# RemoteSch_1R1.net
KiCad netlist of a schematic drawn in Altium Designer
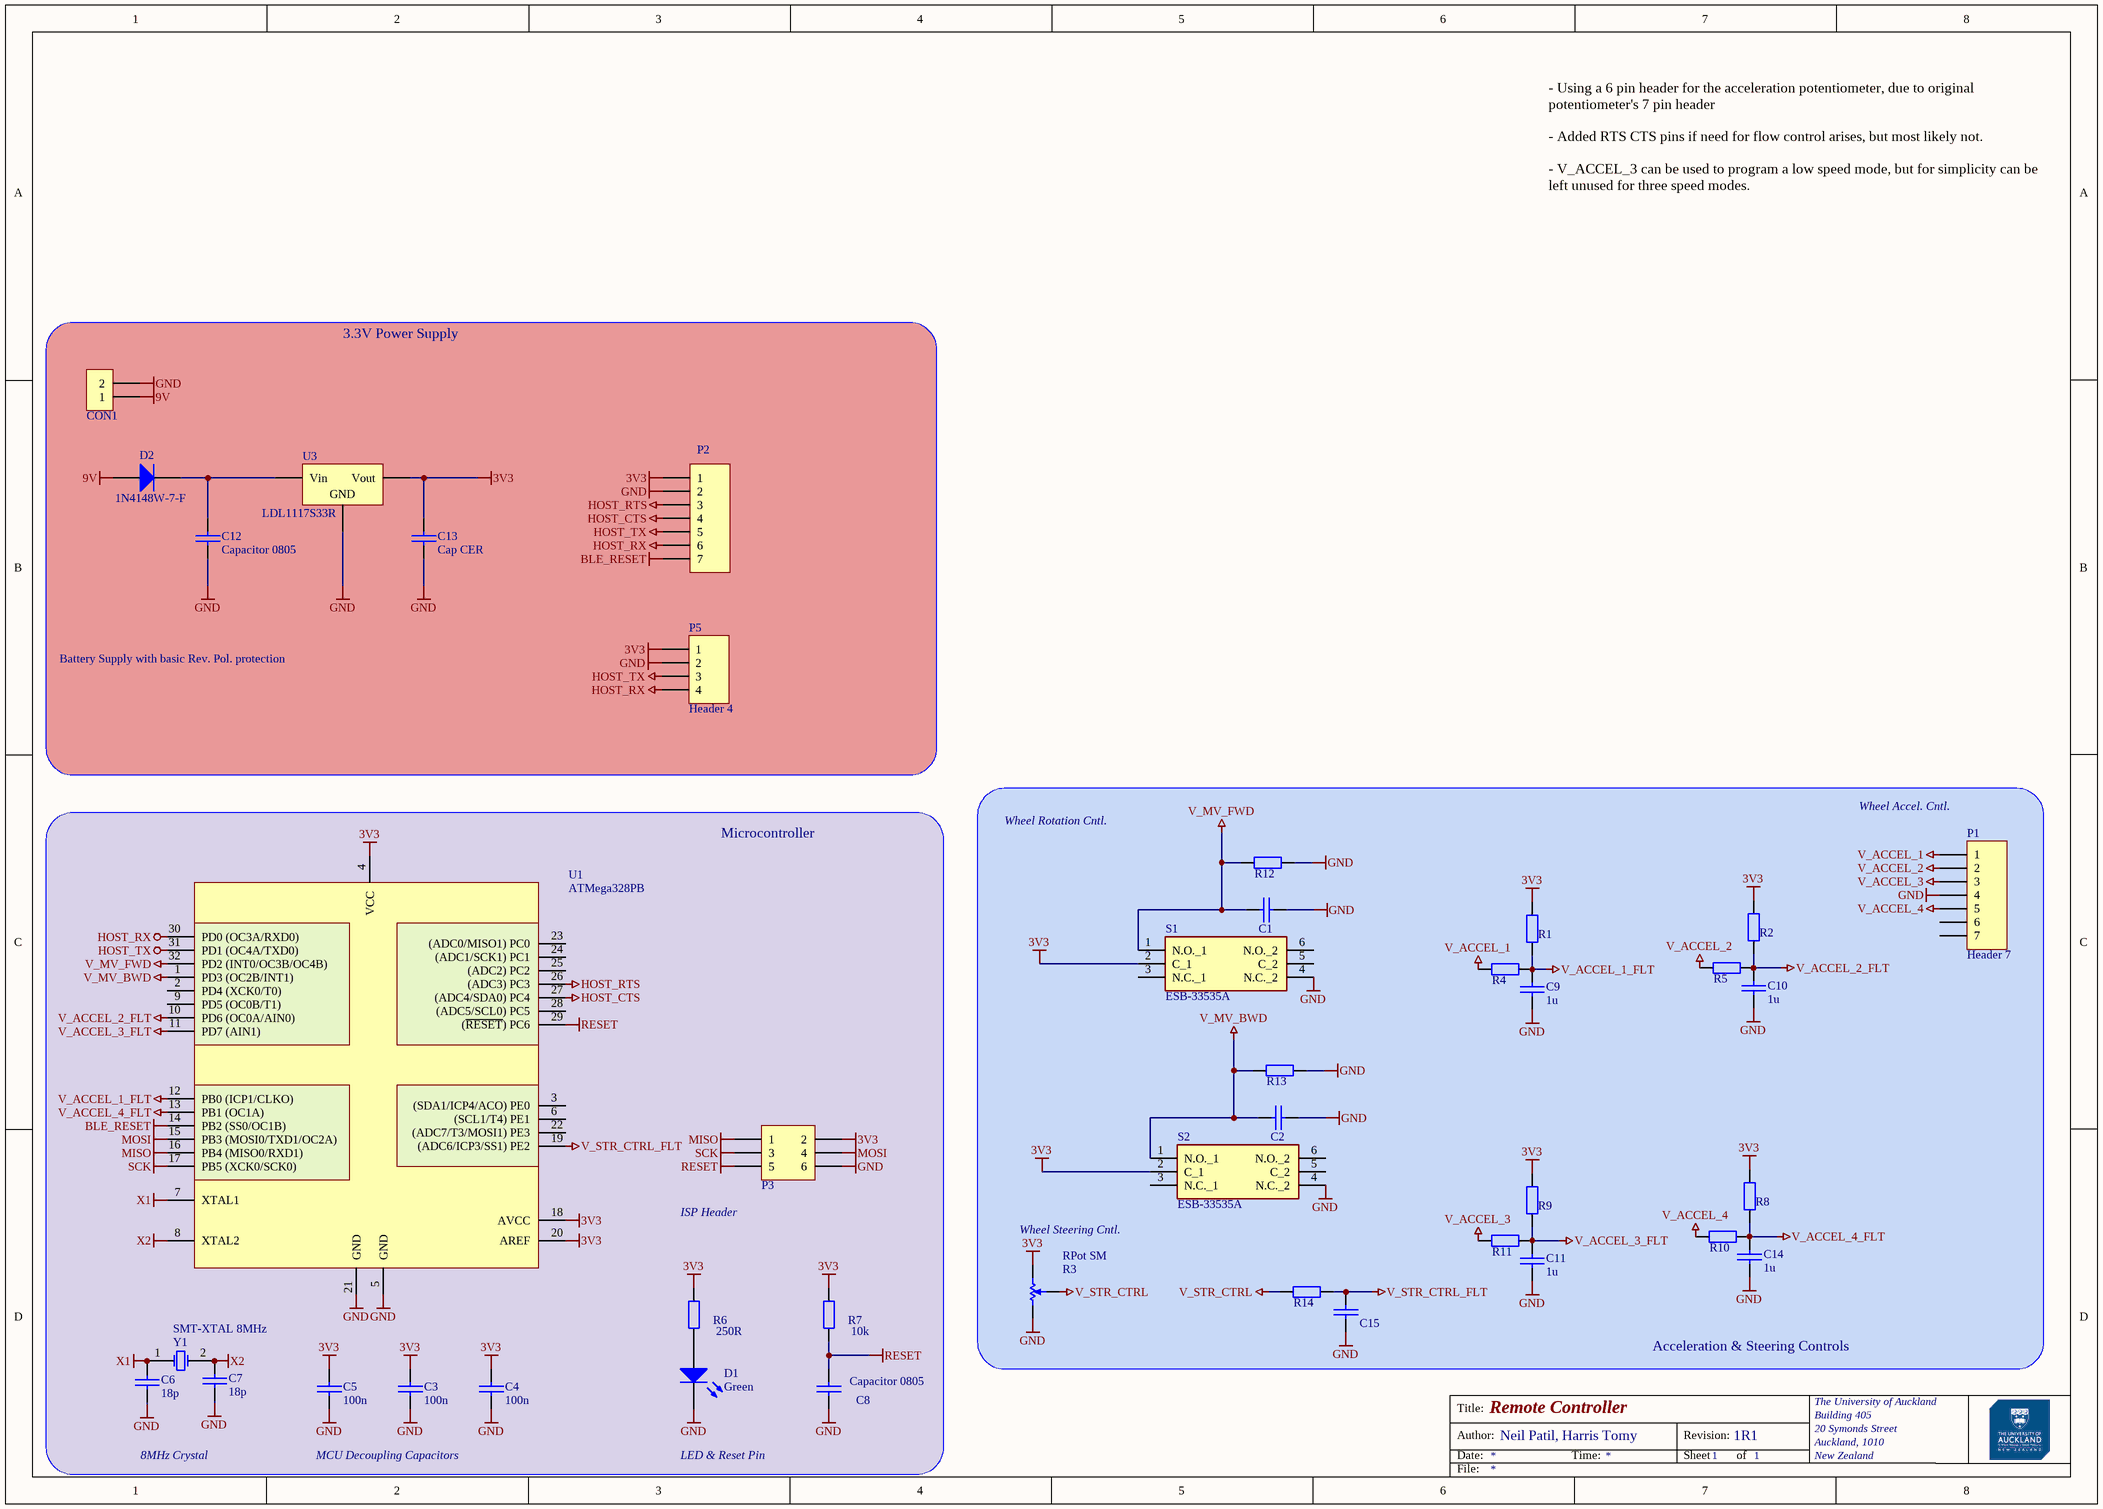
[diagram p0: RemoteSch_1R1.SchDoc]

(export (version "E")
  (design (tool "Eeschema 10.0.6"))
  (components
    (comp (ref "C1")
      (value "Capacitor 0805")
      (footprint "C0805")
      (description "CCAP0805")
      (libsource (lib "CommonDevices_V1") (part "CCAP0805"))
    )
    (comp (ref "C2")
      (value "Capacitor 0805")
      (footprint "C0805")
      (description "CCAP0805")
      (libsource (lib "CommonDevices_V1") (part "CCAP0805"))
    )
    (comp (ref "C3")
      (value "100n")
      (footprint "C0805")
      (description "CCAP0805")
      (libsource (lib "CommonDevices_V1") (part "CCAP0805"))
    )
    (comp (ref "C4")
      (value "100n")
      (footprint "C0805")
      (description "CCAP0805")
      (libsource (lib "CommonDevices_V1") (part "CCAP0805"))
    )
    (comp (ref "C5")
      (value "100n")
      (footprint "C0805")
      (description "CCAP0805")
      (libsource (lib "CommonDevices_V1") (part "CCAP0805"))
    )
    (comp (ref "C6")
      (value "18p")
      (footprint "C0805")
      (description "CCAP0805")
      (libsource (lib "CommonDevices_V1") (part "CCAP0805"))
    )
    (comp (ref "C7")
      (value "18p")
      (footprint "C0805")
      (description "CCAP0805")
      (libsource (lib "CommonDevices_V1") (part "CCAP0805"))
    )
    (comp (ref "C8")
      (value "Capacitor 0805")
      (footprint "C0805")
      (description "CCAP0805")
      (libsource (lib "CommonDevices_V1") (part "CCAP0805"))
    )
    (comp (ref "C9")
      (value "1u")
      (footprint "C0805")
      (description "CCAP0805")
      (libsource (lib "CommonDevices_V1") (part "CCAP0805"))
    )
    (comp (ref "C10")
      (value "1u")
      (footprint "C0805")
      (description "CCAP0805")
      (libsource (lib "CommonDevices_V1") (part "CCAP0805"))
    )
    (comp (ref "C11")
      (value "1u")
      (footprint "C0805")
      (description "CCAP0805")
      (libsource (lib "CommonDevices_V1") (part "CCAP0805"))
    )
    (comp (ref "C12")
      (value "Capacitor 0805")
      (footprint "C0805")
      (description "CCAP0805")
      (libsource (lib "CommonDevices_V1") (part "CCAP0805"))
    )
    (comp (ref "C13")
      (value "Cap CER")
      (footprint "C1206")
      (description "CAP CER 0.1UF 100V C0G 1206")
      (fields (field (name "MPN") "C3216C0G2A104J160AC") (field (name "MANUFACTURER") "TDK Corporation"))
      (libsource (lib "E209_Lib") (part "Cap CER Decoup C3216C0G2A104J160AC"))
    )
    (comp (ref "C14")
      (value "1u")
      (footprint "C0805")
      (description "CCAP0805")
      (libsource (lib "CommonDevices_V1") (part "CCAP0805"))
    )
    (comp (ref "C15")
      (value "Capacitor 0805")
      (footprint "C0805")
      (description "CCAP0805")
      (libsource (lib "CommonDevices_V1") (part "CCAP0805"))
    )
    (comp (ref "CON1")
      (value "Header 2X1")
      (footprint "HDR2X1_2P54")
      (libsource (lib "CommonDevices_V1") (part "HDR2X1"))
    )
    (comp (ref "D1")
      (value "Green")
      (footprint "LED")
      (description "Typical throughole GaAs LED with 2.54mm pitch")
      (fields (field (name "MANUFACTURER") "Generic Components") (field (name "PUBLISHER") "Altium Limited"))
      (libsource (lib "EE209_Library") (part "LED_TH_2P54"))
    )
    (comp (ref "D2")
      (value "1N4148W-7-F")
      (footprint "SOD123")
      (description "DIODE GEN PURP 100V 300MA SOD123")
      (fields
        (field (name "MANUFACTURER") "Diodes Incorporated")
        (field (name "MANUFACTURER PART NUMBER") "1N4148W-13-F")
      )
      (libsource (lib "EE209_Library") (part "1N4148_SMT_SOD123"))
    )
    (comp (ref "P1")
      (value "Header 7")
      (footprint "HDR1X7")
      (description "Header, 7-Pin")
      (fields (field (name "PUBLISHER") "Altium Limited"))
      (libsource (lib "Miscellaneous Connectors") (part "Header 7"))
    )
    (comp (ref "P2")
      (value "Header 7")
      (footprint "HDR1X7")
      (description "Header, 7-Pin")
      (fields (field (name "PUBLISHER") "Altium Limited"))
      (libsource (lib "Miscellaneous Connectors") (part "Header 7"))
    )
    (comp (ref "P3")
      (value "HDR3X2")
      (footprint "HDR2X3_2P54")
      (description "Header, 3-Pin, Dual row")
      (libsource (lib "CommonDevices_V1") (part "HDR3X2"))
    )
    (comp (ref "P5")
      (value "Header 4")
      (footprint "HDR1X4")
      (description "Header, 4-Pin")
      (fields (field (name "PUBLISHER") "Altium Limited"))
      (libsource (lib "Miscellaneous Connectors") (part "Header 4"))
    )
    (comp (ref "R1")
      (value "Resistor 0805")
      (footprint "R0805")
      (description "RES0805")
      (libsource (lib "CommonDevices_V1") (part "RES0805"))
    )
    (comp (ref "R2")
      (value "Resistor 0805")
      (footprint "R0805")
      (description "RES0805")
      (libsource (lib "CommonDevices_V1") (part "RES0805"))
    )
    (comp (ref "R3")
      (value "RPot SM")
      (footprint "POT4MM-2")
      (description "Square Trimming Potentiometer")
      (fields (field (name "PUBLISHER") "Altium Limited"))
      (libsource (lib "Miscellaneous Devices") (part "RPot SM"))
    )
    (comp (ref "R4")
      (value "Resistor 0805")
      (footprint "R0805")
      (description "RES0805")
      (libsource (lib "") (part "RES0805_1"))
    )
    (comp (ref "R5")
      (value "Resistor 0805")
      (footprint "R0805")
      (description "RES0805")
      (libsource (lib "") (part "RES0805_1"))
    )
    (comp (ref "R6")
      (value "250R")
      (footprint "R0805")
      (description "RES0805")
      (libsource (lib "CommonDevices_V1") (part "RES0805"))
    )
    (comp (ref "R7")
      (value "10k")
      (footprint "R0805")
      (description "RES0805")
      (libsource (lib "CommonDevices_V1") (part "RES0805"))
    )
    (comp (ref "R8")
      (value "Resistor 0805")
      (footprint "R0805")
      (description "RES0805")
      (libsource (lib "CommonDevices_V1") (part "RES0805"))
    )
    (comp (ref "R9")
      (value "Resistor 0805")
      (footprint "R0805")
      (description "RES0805")
      (libsource (lib "CommonDevices_V1") (part "RES0805"))
    )
    (comp (ref "R10")
      (value "Resistor 0805")
      (footprint "R0805")
      (description "RES0805")
      (libsource (lib "") (part "RES0805_1"))
    )
    (comp (ref "R11")
      (value "Resistor 0805")
      (footprint "R0805")
      (description "RES0805")
      (libsource (lib "") (part "RES0805_1"))
    )
    (comp (ref "R12")
      (value "Resistor 0805")
      (footprint "R0805")
      (description "RES0805")
      (libsource (lib "") (part "RES0805_1"))
    )
    (comp (ref "R13")
      (value "Resistor 0805")
      (footprint "R0805")
      (description "RES0805")
      (libsource (lib "") (part "RES0805_1"))
    )
    (comp (ref "R14")
      (value "Resistor 0805")
      (footprint "R0805")
      (description "RES0805")
      (libsource (lib "") (part "RES0805_2"))
    )
    (comp (ref "S1")
      (value "ESB-33535A")
      (footprint "ESB33535A")
      (description "Switch")
      (fields (field (name "MOUSER PART NUMBER") "667-ESB-33535A"))
      (libsource (lib "ESB-3353A") (part "ESB-33535A"))
    )
    (comp (ref "S2")
      (value "ESB-33535A")
      (footprint "ESB33535A")
      (description "Switch")
      (fields (field (name "MOUSER PART NUMBER") "667-ESB-33535A"))
      (libsource (lib "ESB-3353A") (part "ESB-33535A"))
    )
    (comp (ref "U1")
      (value "ATMega328PB")
      (footprint "TQFP32")
      (description "IC MCU 8BIT 32KB FLASH 32TQFP")
      (libsource (lib "CommonDevices_V1") (part "ATMega328PB"))
    )
    (comp (ref "U3")
      (value "LDL1117S33R")
      (footprint "SOT223L")
      (description "IC REG LINEAR 3.3V 1.2A SOT223")
      (fields (field (name "MANUFACTURER") "STMicroelectronics"))
      (libsource (lib "E209_Lib") (part "LDO LDL1117S33R"))
    )
    (comp (ref "Y1")
      (value "SMT-XTAL 8MHz")
      (footprint "HC49-US")
      (description "9C-16.000MAAJ-T crystal 16.0000MHZ 18PF SMD")
      (fields
        (field (name "MANUFACTURER") "TXC CORPORATION")
        (field (name "MANUFACTURER PART NUMBER") "9C-16.000MAAJ-T")
      )
      (libsource (lib "EE209_Library") (part "TXC9C-16_XTAL_SMT"))
    )
  )
  (nets
    (net (code "1") (name "3V3") (class "Default")
      (node (ref "C13") (pin "2") (pinfunction "2_2") (pintype "passive"))
      (node (ref "C3") (pin "2") (pinfunction "2_2") (pintype "passive"))
      (node (ref "C4") (pin "2") (pinfunction "2_2") (pintype "passive"))
      (node (ref "C5") (pin "2") (pinfunction "2_2") (pintype "passive"))
      (node (ref "P2") (pin "1") (pinfunction "1_1") (pintype "passive"))
      (node (ref "P3") (pin "2") (pinfunction "2_2") (pintype "passive"))
      (node (ref "P5") (pin "1") (pinfunction "1_1") (pintype "passive"))
      (node (ref "R1") (pin "2") (pinfunction "2_2") (pintype "passive"))
      (node (ref "R2") (pin "2") (pinfunction "2_2") (pintype "passive"))
      (node (ref "R3") (pin "CW") (pinfunction "+_CW") (pintype "passive"))
      (node (ref "R6") (pin "2") (pinfunction "2_2") (pintype "passive"))
      (node (ref "R7") (pin "2") (pinfunction "2_2") (pintype "passive"))
      (node (ref "R8") (pin "2") (pinfunction "2_2") (pintype "passive"))
      (node (ref "R9") (pin "2") (pinfunction "2_2") (pintype "passive"))
      (node (ref "S1") (pin "2") (pinfunction "C_1_2") (pintype "passive"))
      (node (ref "S2") (pin "2") (pinfunction "C_1_2") (pintype "passive"))
      (node (ref "U1") (pin "18") (pinfunction "AVCC_18") (pintype "passive"))
      (node (ref "U1") (pin "20") (pinfunction "AREF_20") (pintype "passive"))
      (node (ref "U1") (pin "4") (pinfunction "VCC_4") (pintype "passive"))
      (node (ref "U3") (pin "2") (pinfunction "Vout_2") (pintype "passive"))
    )
    (net (code "2") (name "9V") (class "Default")
      (node (ref "CON1") (pin "1") (pinfunction "1_1") (pintype "passive"))
      (node (ref "D2") (pin "1") (pinfunction "A_1") (pintype "passive"))
    )
    (net (code "3") (name "BLE_RESET") (class "Default")
      (node (ref "P2") (pin "7") (pinfunction "7_7") (pintype "passive"))
      (node (ref "U1") (pin "14") (pinfunction "PB2_(SS0/OC1B)_14") (pintype "passive"))
    )
    (net (code "4") (name "GND") (class "Default")
      (node (ref "C1") (pin "1") (pinfunction "1_1") (pintype "passive"))
      (node (ref "C10") (pin "1") (pinfunction "1_1") (pintype "passive"))
      (node (ref "C11") (pin "1") (pinfunction "1_1") (pintype "passive"))
      (node (ref "C12") (pin "1") (pinfunction "1_1") (pintype "passive"))
      (node (ref "C13") (pin "1") (pinfunction "1_1") (pintype "passive"))
      (node (ref "C14") (pin "1") (pinfunction "1_1") (pintype "passive"))
      (node (ref "C15") (pin "1") (pinfunction "1_1") (pintype "passive"))
      (node (ref "C2") (pin "1") (pinfunction "1_1") (pintype "passive"))
      (node (ref "C3") (pin "1") (pinfunction "1_1") (pintype "passive"))
      (node (ref "C4") (pin "1") (pinfunction "1_1") (pintype "passive"))
      (node (ref "C5") (pin "1") (pinfunction "1_1") (pintype "passive"))
      (node (ref "C6") (pin "2") (pinfunction "2_2") (pintype "passive"))
      (node (ref "C7") (pin "2") (pinfunction "2_2") (pintype "passive"))
      (node (ref "C8") (pin "1") (pinfunction "1_1") (pintype "passive"))
      (node (ref "C9") (pin "1") (pinfunction "1_1") (pintype "passive"))
      (node (ref "CON1") (pin "2") (pinfunction "2_2") (pintype "passive"))
      (node (ref "D1") (pin "2") (pinfunction "K_2") (pintype "passive"))
      (node (ref "P1") (pin "4") (pinfunction "4_4") (pintype "passive"))
      (node (ref "P2") (pin "2") (pinfunction "2_2") (pintype "passive"))
      (node (ref "P3") (pin "6") (pinfunction "6_6") (pintype "passive"))
      (node (ref "P5") (pin "2") (pinfunction "2_2") (pintype "passive"))
      (node (ref "R12") (pin "1") (pinfunction "1_1") (pintype "passive"))
      (node (ref "R13") (pin "1") (pinfunction "1_1") (pintype "passive"))
      (node (ref "R3") (pin "CCW") (pinfunction "-_CCW") (pintype "passive"))
      (node (ref "S1") (pin "4") (pinfunction "N.C._2_4") (pintype "passive"))
      (node (ref "S2") (pin "4") (pinfunction "N.C._2_4") (pintype "passive"))
      (node (ref "U1") (pin "21") (pinfunction "GND_21") (pintype "passive"))
      (node (ref "U1") (pin "5") (pinfunction "GND_5") (pintype "passive"))
      (node (ref "U3") (pin "1") (pinfunction "GND_1") (pintype "passive"))
    )
    (net (code "5") (name "HOST_CTS") (class "Default")
      (node (ref "P2") (pin "4") (pinfunction "4_4") (pintype "passive"))
      (node (ref "U1") (pin "27") (pinfunction "(ADC4/SDA0)_PC4_27") (pintype "passive"))
    )
    (net (code "6") (name "HOST_RTS") (class "Default")
      (node (ref "P2") (pin "3") (pinfunction "3_3") (pintype "passive"))
      (node (ref "U1") (pin "26") (pinfunction "(ADC3)_PC3_26") (pintype "passive"))
    )
    (net (code "7") (name "HOST_RX") (class "Default")
      (node (ref "P2") (pin "6") (pinfunction "6_6") (pintype "passive"))
      (node (ref "P5") (pin "4") (pinfunction "4_4") (pintype "passive"))
      (node (ref "U1") (pin "30") (pinfunction "PD0_(OC3A/RXD0)_30") (pintype "passive"))
    )
    (net (code "8") (name "HOST_TX") (class "Default")
      (node (ref "P2") (pin "5") (pinfunction "5_5") (pintype "passive"))
      (node (ref "P5") (pin "3") (pinfunction "3_3") (pintype "passive"))
      (node (ref "U1") (pin "31") (pinfunction "PD1_(OC4A/TXD0)_31") (pintype "passive"))
    )
    (net (code "9") (name "MISO") (class "Default")
      (node (ref "P3") (pin "1") (pinfunction "1_1") (pintype "passive"))
      (node (ref "U1") (pin "16") (pinfunction "PB4_(MISO0/RXD1)_16") (pintype "passive"))
    )
    (net (code "10") (name "MOSI") (class "Default")
      (node (ref "P3") (pin "4") (pinfunction "4_4") (pintype "passive"))
      (node (ref "U1") (pin "15") (pinfunction "PB3_(MOSI0/TXD1/OC2A)_15") (pintype "passive"))
    )
    (net (code "11") (name "Net-(D1-A)") (class "Default")
      (node (ref "D1") (pin "1") (pinfunction "A_1") (pintype "passive"))
      (node (ref "R6") (pin "1") (pinfunction "1_1") (pintype "passive"))
    )
    (net (code "12") (name "Net-(D2-K)") (class "Default")
      (node (ref "C12") (pin "2") (pinfunction "2_2") (pintype "passive"))
      (node (ref "D2") (pin "2") (pinfunction "K_2") (pintype "passive"))
      (node (ref "U3") (pin "3") (pinfunction "Vin_3") (pintype "passive"))
    )
    (net (code "13") (name "RESET") (class "Default")
      (node (ref "C8") (pin "2") (pinfunction "2_2") (pintype "passive"))
      (node (ref "P3") (pin "5") (pinfunction "5_5") (pintype "passive"))
      (node (ref "R7") (pin "1") (pinfunction "1_1") (pintype "passive"))
      (node (ref "U1") (pin "29") (pinfunction "(~{RESET})_PC6_29") (pintype "passive"))
    )
    (net (code "14") (name "SCK") (class "Default")
      (node (ref "P3") (pin "3") (pinfunction "3_3") (pintype "passive"))
      (node (ref "U1") (pin "17") (pinfunction "PB5_(XCK0/SCK0)_17") (pintype "passive"))
    )
    (net (code "15") (name "V_ACCEL_1") (class "Default")
      (node (ref "P1") (pin "1") (pinfunction "1_1") (pintype "passive"))
      (node (ref "R4") (pin "2") (pinfunction "2_2") (pintype "passive"))
    )
    (net (code "16") (name "V_ACCEL_1_FLT") (class "Default")
      (node (ref "C9") (pin "2") (pinfunction "2_2") (pintype "passive"))
      (node (ref "R1") (pin "1") (pinfunction "1_1") (pintype "passive"))
      (node (ref "R4") (pin "1") (pinfunction "1_1") (pintype "passive"))
      (node (ref "U1") (pin "12") (pinfunction "PB0_(ICP1/CLKO)_12") (pintype "passive"))
    )
    (net (code "17") (name "V_ACCEL_2") (class "Default")
      (node (ref "P1") (pin "2") (pinfunction "2_2") (pintype "passive"))
      (node (ref "R5") (pin "2") (pinfunction "2_2") (pintype "passive"))
    )
    (net (code "18") (name "V_ACCEL_2_FLT") (class "Default")
      (node (ref "C10") (pin "2") (pinfunction "2_2") (pintype "passive"))
      (node (ref "R2") (pin "1") (pinfunction "1_1") (pintype "passive"))
      (node (ref "R5") (pin "1") (pinfunction "1_1") (pintype "passive"))
      (node (ref "U1") (pin "10") (pinfunction "PD6_(OC0A/AIN0)_10") (pintype "passive"))
    )
    (net (code "19") (name "V_ACCEL_3") (class "Default")
      (node (ref "P1") (pin "3") (pinfunction "3_3") (pintype "passive"))
      (node (ref "R11") (pin "2") (pinfunction "2_2") (pintype "passive"))
    )
    (net (code "20") (name "V_ACCEL_3_FLT") (class "Default")
      (node (ref "C11") (pin "2") (pinfunction "2_2") (pintype "passive"))
      (node (ref "R11") (pin "1") (pinfunction "1_1") (pintype "passive"))
      (node (ref "R9") (pin "1") (pinfunction "1_1") (pintype "passive"))
      (node (ref "U1") (pin "11") (pinfunction "PD7_(AIN1)_11") (pintype "passive"))
    )
    (net (code "21") (name "V_ACCEL_4") (class "Default")
      (node (ref "P1") (pin "5") (pinfunction "5_5") (pintype "passive"))
      (node (ref "R10") (pin "2") (pinfunction "2_2") (pintype "passive"))
    )
    (net (code "22") (name "V_ACCEL_4_FLT") (class "Default")
      (node (ref "C14") (pin "2") (pinfunction "2_2") (pintype "passive"))
      (node (ref "R10") (pin "1") (pinfunction "1_1") (pintype "passive"))
      (node (ref "R8") (pin "1") (pinfunction "1_1") (pintype "passive"))
      (node (ref "U1") (pin "13") (pinfunction "PB1_(OC1A)_13") (pintype "passive"))
    )
    (net (code "23") (name "V_MV_BWD") (class "Default")
      (node (ref "C2") (pin "2") (pinfunction "2_2") (pintype "passive"))
      (node (ref "R13") (pin "2") (pinfunction "2_2") (pintype "passive"))
      (node (ref "S2") (pin "1") (pinfunction "N.O._1_1") (pintype "passive"))
      (node (ref "U1") (pin "1") (pinfunction "PD3_(OC2B/INT1)_1") (pintype "passive"))
    )
    (net (code "24") (name "V_MV_FWD") (class "Default")
      (node (ref "C1") (pin "2") (pinfunction "2_2") (pintype "passive"))
      (node (ref "R12") (pin "2") (pinfunction "2_2") (pintype "passive"))
      (node (ref "S1") (pin "1") (pinfunction "N.O._1_1") (pintype "passive"))
      (node (ref "U1") (pin "32") (pinfunction "PD2_(INT0/OC3B/OC4B)_32") (pintype "passive"))
    )
    (net (code "25") (name "V_STR_CTRL") (class "Default")
      (node (ref "R14") (pin "1") (pinfunction "1_1") (pintype "passive"))
      (node (ref "R3") (pin "W") (pinfunction "W_W") (pintype "passive"))
    )
    (net (code "26") (name "V_STR_CTRL_FLT") (class "Default")
      (node (ref "C15") (pin "2") (pinfunction "2_2") (pintype "passive"))
      (node (ref "R14") (pin "2") (pinfunction "2_2") (pintype "passive"))
      (node (ref "U1") (pin "19") (pinfunction "(ADC6/ICP3/SS1)_PE2_19") (pintype "passive"))
    )
    (net (code "27") (name "X1") (class "Default")
      (node (ref "C6") (pin "1") (pinfunction "1_1") (pintype "passive"))
      (node (ref "U1") (pin "7") (pinfunction "XTAL1_7") (pintype "passive"))
      (node (ref "Y1") (pin "1") (pinfunction "OSC1_1") (pintype "passive"))
    )
    (net (code "28") (name "X2") (class "Default")
      (node (ref "C7") (pin "1") (pinfunction "1_1") (pintype "passive"))
      (node (ref "U1") (pin "8") (pinfunction "XTAL2_8") (pintype "passive"))
      (node (ref "Y1") (pin "2") (pinfunction "OSC2_2") (pintype "passive"))
    )
    (net (code "29") (name "unconnected-(P1-Pad6)") (class "Default")
      (node (ref "P1") (pin "6") (pinfunction "6_6") (pintype "passive"))
    )
    (net (code "30") (name "unconnected-(P1-Pad7)") (class "Default")
      (node (ref "P1") (pin "7") (pinfunction "7_7") (pintype "passive"))
    )
    (net (code "31") (name "unconnected-(S1-C_2-Pad5)") (class "Default")
      (node (ref "S1") (pin "5") (pinfunction "C_2_5") (pintype "passive"))
    )
    (net (code "32") (name "unconnected-(S1-N.C._1-Pad3)") (class "Default")
      (node (ref "S1") (pin "3") (pinfunction "N.C._1_3") (pintype "passive"))
    )
    (net (code "33") (name "unconnected-(S1-N.O._2-Pad6)") (class "Default")
      (node (ref "S1") (pin "6") (pinfunction "N.O._2_6") (pintype "passive"))
    )
    (net (code "34") (name "unconnected-(S2-C_2-Pad5)") (class "Default")
      (node (ref "S2") (pin "5") (pinfunction "C_2_5") (pintype "passive"))
    )
    (net (code "35") (name "unconnected-(S2-N.C._1-Pad3)") (class "Default")
      (node (ref "S2") (pin "3") (pinfunction "N.C._1_3") (pintype "passive"))
    )
    (net (code "36") (name "unconnected-(S2-N.O._2-Pad6)") (class "Default")
      (node (ref "S2") (pin "6") (pinfunction "N.O._2_6") (pintype "passive"))
    )
    (net (code "37") (name "unconnected-(U1-(ADC0{slash}MISO1)_PC0-Pad23)") (class "Default")
      (node (ref "U1") (pin "23") (pinfunction "(ADC0/MISO1)_PC0_23") (pintype "passive"))
    )
    (net (code "38") (name "unconnected-(U1-(ADC1{slash}SCK1)_PC1-Pad24)") (class "Default")
      (node (ref "U1") (pin "24") (pinfunction "(ADC1/SCK1)_PC1_24") (pintype "passive"))
    )
    (net (code "39") (name "unconnected-(U1-(ADC2)_PC2-Pad25)") (class "Default")
      (node (ref "U1") (pin "25") (pinfunction "(ADC2)_PC2_25") (pintype "passive"))
    )
    (net (code "40") (name "unconnected-(U1-(ADC5{slash}SCL0)_PC5-Pad28)") (class "Default")
      (node (ref "U1") (pin "28") (pinfunction "(ADC5/SCL0)_PC5_28") (pintype "passive"))
    )
    (net (code "41") (name "unconnected-(U1-(ADC7{slash}T3{slash}MOSI1)_PE3-Pad22)") (class "Default")
      (node (ref "U1") (pin "22") (pinfunction "(ADC7/T3/MOSI1)_PE3_22") (pintype "passive"))
    )
    (net (code "42") (name "unconnected-(U1-(SCL1{slash}T4)_PE1-Pad6)") (class "Default")
      (node (ref "U1") (pin "6") (pinfunction "(SCL1/T4)_PE1_6") (pintype "passive"))
    )
    (net (code "43") (name "unconnected-(U1-(SDA1{slash}ICP4{slash}ACO)_PE0-Pad3)") (class "Default")
      (node (ref "U1") (pin "3") (pinfunction "(SDA1/ICP4/ACO)_PE0_3") (pintype "passive"))
    )
    (net (code "44") (name "unconnected-(U1-PD4_(XCK0{slash}T0)-Pad2)") (class "Default")
      (node (ref "U1") (pin "2") (pinfunction "PD4_(XCK0/T0)_2") (pintype "passive"))
    )
    (net (code "45") (name "unconnected-(U1-PD5_(OC0B{slash}T1)-Pad9)") (class "Default")
      (node (ref "U1") (pin "9") (pinfunction "PD5_(OC0B/T1)_9") (pintype "passive"))
    )
  )
)
